# TRI_LED.net
KiCad netlist of a schematic drawn in EAGLE
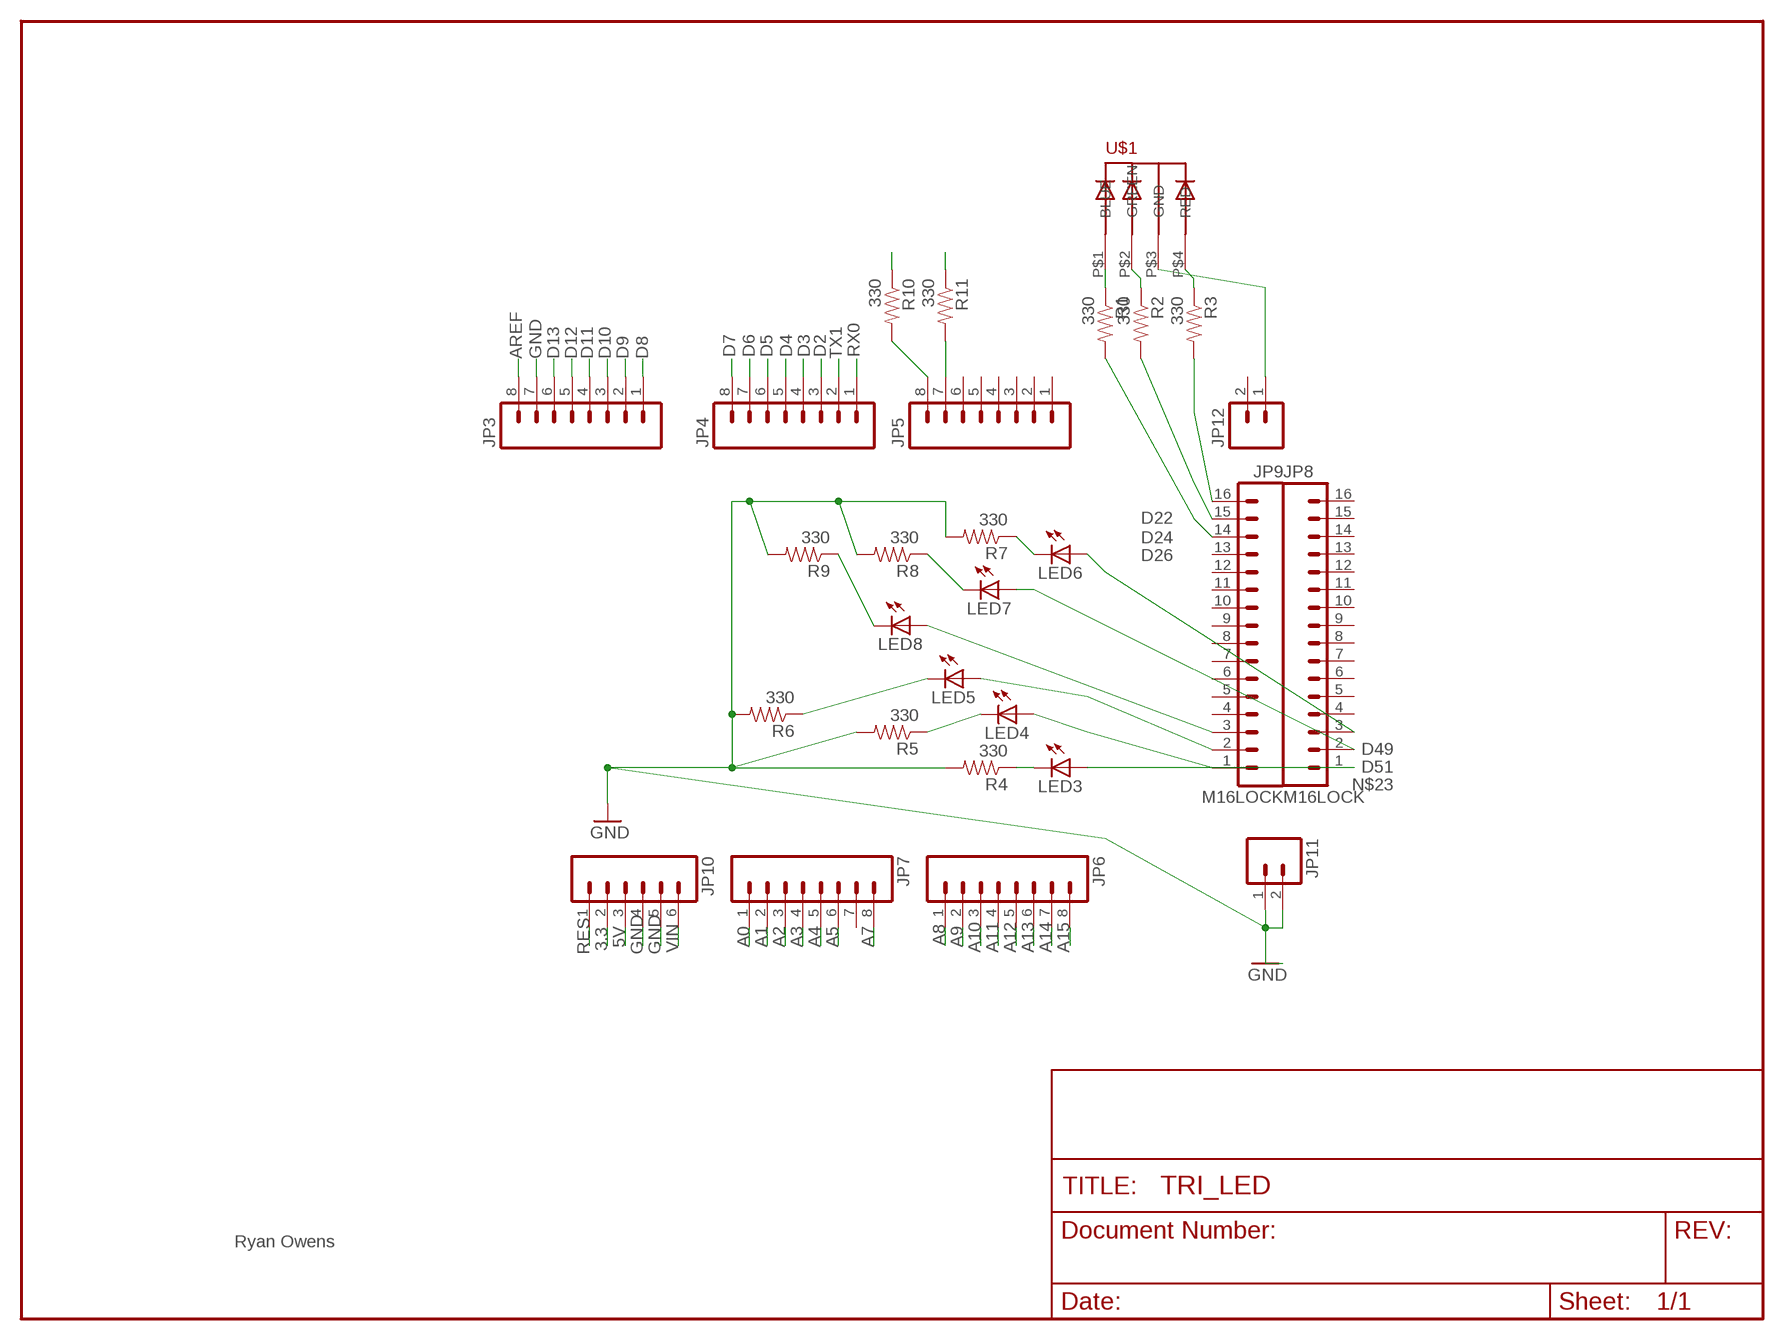
[diagram p0: schematic, sheet 1]

(export (version "E")
  (design (tool "Eeschema 10.0.6"))
  (components
    (comp (ref "JP3")
      (value "M08LOCK")
      (footprint "eagle-import:1X08_LOCK")
      (libsource (lib "eagle-import") (part "M08LOCK"))
    )
    (comp (ref "JP4")
      (value "M08LOCK")
      (footprint "eagle-import:1X08_LOCK")
      (libsource (lib "eagle-import") (part "M08LOCK"))
    )
    (comp (ref "JP5")
      (value "M08LOCK")
      (footprint "eagle-import:1X08_LOCK")
      (libsource (lib "eagle-import") (part "M08LOCK"))
    )
    (comp (ref "JP6")
      (value "M08LOCK")
      (footprint "eagle-import:1X08_LOCK")
      (libsource (lib "eagle-import") (part "M08LOCK"))
    )
    (comp (ref "JP7")
      (value "M08LOCK")
      (footprint "eagle-import:1X08_LOCK")
      (libsource (lib "eagle-import") (part "M08LOCK"))
    )
    (comp (ref "JP8")
      (value "M16LOCK")
      (footprint "eagle-import:1X16_LOCK")
      (libsource (lib "eagle-import") (part "M16LOCK"))
    )
    (comp (ref "JP9")
      (value "M16LOCK")
      (footprint "eagle-import:1X16_LOCK")
      (libsource (lib "eagle-import") (part "M16LOCK"))
    )
    (comp (ref "JP10")
      (value "M06LOCK")
      (footprint "eagle-import:1X06_LOCK")
      (libsource (lib "eagle-import") (part "M06LOCK"))
    )
    (comp (ref "JP11")
      (value "M02LOCK")
      (footprint "eagle-import:1X02_LOCK")
      (libsource (lib "eagle-import") (part "M02LOCK"))
    )
    (comp (ref "JP12")
      (value "M02LOCK")
      (footprint "eagle-import:1X02_LOCK")
      (libsource (lib "eagle-import") (part "M02LOCK"))
    )
    (comp (ref "LED3")
      (value "LED5MM")
      (footprint "eagle-import:LED5MM")
      (libsource (lib "eagle-import") (part "LED5MM"))
    )
    (comp (ref "LED4")
      (value "LED5MM")
      (footprint "eagle-import:LED5MM")
      (libsource (lib "eagle-import") (part "LED5MM"))
    )
    (comp (ref "LED5")
      (value "LED5MM")
      (footprint "eagle-import:LED5MM")
      (libsource (lib "eagle-import") (part "LED5MM"))
    )
    (comp (ref "LED6")
      (value "LED5MM")
      (footprint "eagle-import:LED5MM")
      (libsource (lib "eagle-import") (part "LED5MM"))
    )
    (comp (ref "LED7")
      (value "LED5MM")
      (footprint "eagle-import:LED5MM")
      (libsource (lib "eagle-import") (part "LED5MM"))
    )
    (comp (ref "LED8")
      (value "LED5MM")
      (footprint "eagle-import:LED5MM")
      (libsource (lib "eagle-import") (part "LED5MM"))
    )
    (comp (ref "R1")
      (value "330")
      (footprint "eagle-import:AXIAL-0.3")
      (libsource (lib "eagle-import") (part "RESISTORPTH1"))
    )
    (comp (ref "R2")
      (value "330")
      (footprint "eagle-import:AXIAL-0.3")
      (libsource (lib "eagle-import") (part "RESISTORPTH1"))
    )
    (comp (ref "R3")
      (value "330")
      (footprint "eagle-import:AXIAL-0.3")
      (libsource (lib "eagle-import") (part "RESISTORPTH1"))
    )
    (comp (ref "R4")
      (value "330")
      (footprint "eagle-import:AXIAL-0.3")
      (libsource (lib "eagle-import") (part "RESISTORPTH1"))
    )
    (comp (ref "R5")
      (value "330")
      (footprint "eagle-import:AXIAL-0.3")
      (libsource (lib "eagle-import") (part "RESISTORPTH1"))
    )
    (comp (ref "R6")
      (value "330")
      (footprint "eagle-import:AXIAL-0.3")
      (libsource (lib "eagle-import") (part "RESISTORPTH1"))
    )
    (comp (ref "R7")
      (value "330")
      (footprint "eagle-import:AXIAL-0.3")
      (libsource (lib "eagle-import") (part "RESISTORPTH1"))
    )
    (comp (ref "R8")
      (value "330")
      (footprint "eagle-import:AXIAL-0.3")
      (libsource (lib "eagle-import") (part "RESISTORPTH1"))
    )
    (comp (ref "R9")
      (value "330")
      (footprint "eagle-import:AXIAL-0.3")
      (libsource (lib "eagle-import") (part "RESISTORPTH1"))
    )
    (comp (ref "R10")
      (value "330")
      (footprint "eagle-import:AXIAL-0.3")
      (libsource (lib "eagle-import") (part "RESISTORPTH1"))
    )
    (comp (ref "R11")
      (value "330")
      (footprint "eagle-import:AXIAL-0.3")
      (libsource (lib "eagle-import") (part "RESISTORPTH1"))
    )
    (comp (ref "U$1")
      (value "5MMRGBLED")
      (footprint "eagle-import:LED5MMRGB")
      (libsource (lib "eagle-import") (part "5MMRGBLED"))
    )
  )
  (nets
    (net (code "1") (name "/3.3") (class "Default")
      (node (ref "JP10") (pin "2") (pinfunction "2_2") (pintype "passive"))
    )
    (net (code "2") (name "/5V") (class "Default")
      (node (ref "JP10") (pin "3") (pinfunction "3_3") (pintype "passive"))
    )
    (net (code "3") (name "/A0") (class "Default")
      (node (ref "JP7") (pin "1") (pinfunction "1_1") (pintype "passive"))
    )
    (net (code "4") (name "/A1") (class "Default")
      (node (ref "JP7") (pin "2") (pinfunction "2_2") (pintype "passive"))
    )
    (net (code "5") (name "/A2") (class "Default")
      (node (ref "JP7") (pin "3") (pinfunction "3_3") (pintype "passive"))
    )
    (net (code "6") (name "/A3") (class "Default")
      (node (ref "JP7") (pin "4") (pinfunction "4_4") (pintype "passive"))
    )
    (net (code "7") (name "/A4") (class "Default")
      (node (ref "JP7") (pin "5") (pinfunction "5_5") (pintype "passive"))
    )
    (net (code "8") (name "/A5") (class "Default")
      (node (ref "JP7") (pin "6") (pinfunction "6_6") (pintype "passive"))
    )
    (net (code "9") (name "/A7") (class "Default")
      (node (ref "JP7") (pin "8") (pinfunction "8_8") (pintype "passive"))
    )
    (net (code "10") (name "/A8") (class "Default")
      (node (ref "JP6") (pin "1") (pinfunction "1_1") (pintype "passive"))
    )
    (net (code "11") (name "/A9") (class "Default")
      (node (ref "JP6") (pin "2") (pinfunction "2_2") (pintype "passive"))
    )
    (net (code "12") (name "/A10") (class "Default")
      (node (ref "JP6") (pin "3") (pinfunction "3_3") (pintype "passive"))
    )
    (net (code "13") (name "/A11") (class "Default")
      (node (ref "JP6") (pin "4") (pinfunction "4_4") (pintype "passive"))
    )
    (net (code "14") (name "/A12") (class "Default")
      (node (ref "JP6") (pin "5") (pinfunction "5_5") (pintype "passive"))
    )
    (net (code "15") (name "/A13") (class "Default")
      (node (ref "JP6") (pin "6") (pinfunction "6_6") (pintype "passive"))
    )
    (net (code "16") (name "/A14") (class "Default")
      (node (ref "JP6") (pin "7") (pinfunction "7_7") (pintype "passive"))
    )
    (net (code "17") (name "/A15") (class "Default")
      (node (ref "JP6") (pin "8") (pinfunction "8_8") (pintype "passive"))
    )
    (net (code "18") (name "/AREF") (class "Default")
      (node (ref "JP3") (pin "8") (pinfunction "8_8") (pintype "passive"))
    )
    (net (code "19") (name "/D2") (class "Default")
      (node (ref "JP4") (pin "3") (pinfunction "3_3") (pintype "passive"))
    )
    (net (code "20") (name "/D3") (class "Default")
      (node (ref "JP4") (pin "4") (pinfunction "4_4") (pintype "passive"))
    )
    (net (code "21") (name "/D4") (class "Default")
      (node (ref "JP4") (pin "5") (pinfunction "5_5") (pintype "passive"))
    )
    (net (code "22") (name "/D5") (class "Default")
      (node (ref "JP4") (pin "6") (pinfunction "6_6") (pintype "passive"))
    )
    (net (code "23") (name "/D6") (class "Default")
      (node (ref "JP4") (pin "7") (pinfunction "7_7") (pintype "passive"))
    )
    (net (code "24") (name "/D7") (class "Default")
      (node (ref "JP4") (pin "8") (pinfunction "8_8") (pintype "passive"))
    )
    (net (code "25") (name "/D8") (class "Default")
      (node (ref "JP3") (pin "1") (pinfunction "1_1") (pintype "passive"))
    )
    (net (code "26") (name "/D9") (class "Default")
      (node (ref "JP3") (pin "2") (pinfunction "2_2") (pintype "passive"))
    )
    (net (code "27") (name "/D10") (class "Default")
      (node (ref "JP3") (pin "3") (pinfunction "3_3") (pintype "passive"))
    )
    (net (code "28") (name "/D11") (class "Default")
      (node (ref "JP3") (pin "4") (pinfunction "4_4") (pintype "passive"))
    )
    (net (code "29") (name "/D12") (class "Default")
      (node (ref "JP3") (pin "5") (pinfunction "5_5") (pintype "passive"))
    )
    (net (code "30") (name "/D13") (class "Default")
      (node (ref "JP3") (pin "6") (pinfunction "6_6") (pintype "passive"))
    )
    (net (code "31") (name "/D22") (class "Default")
      (node (ref "JP9") (pin "1") (pinfunction "1_1") (pintype "passive"))
      (node (ref "LED4") (pin "A") (pinfunction "A_A") (pintype "passive"))
    )
    (net (code "32") (name "/D24") (class "Default")
      (node (ref "JP9") (pin "2") (pinfunction "2_2") (pintype "passive"))
      (node (ref "LED5") (pin "A") (pinfunction "A_A") (pintype "passive"))
    )
    (net (code "33") (name "/D26") (class "Default")
      (node (ref "JP9") (pin "3") (pinfunction "3_3") (pintype "passive"))
      (node (ref "LED8") (pin "A") (pinfunction "A_A") (pintype "passive"))
    )
    (net (code "34") (name "/D49") (class "Default")
      (node (ref "JP8") (pin "3") (pinfunction "3_3") (pintype "passive"))
      (node (ref "LED6") (pin "A") (pinfunction "A_A") (pintype "passive"))
    )
    (net (code "35") (name "/D51") (class "Default")
      (node (ref "JP8") (pin "2") (pinfunction "2_2") (pintype "passive"))
      (node (ref "LED7") (pin "A") (pinfunction "A_A") (pintype "passive"))
    )
    (net (code "36") (name "/N$23") (class "Default")
      (node (ref "JP8") (pin "1") (pinfunction "1_1") (pintype "passive"))
      (node (ref "LED3") (pin "A") (pinfunction "A_A") (pintype "passive"))
    )
    (net (code "37") (name "/RES") (class "Default")
      (node (ref "JP10") (pin "1") (pinfunction "1_1") (pintype "passive"))
    )
    (net (code "38") (name "/RX0") (class "Default")
      (node (ref "JP4") (pin "1") (pinfunction "1_1") (pintype "passive"))
    )
    (net (code "39") (name "/TX1") (class "Default")
      (node (ref "JP4") (pin "2") (pinfunction "2_2") (pintype "passive"))
    )
    (net (code "40") (name "/VIN") (class "Default")
      (node (ref "JP10") (pin "6") (pinfunction "6_6") (pintype "passive"))
    )
    (net (code "41") (name "GND") (class "Default")
      (node (ref "JP10") (pin "4") (pinfunction "4_4") (pintype "passive"))
      (node (ref "JP10") (pin "5") (pinfunction "5_5") (pintype "passive"))
      (node (ref "JP11") (pin "1") (pinfunction "1_1") (pintype "passive"))
      (node (ref "JP11") (pin "2") (pinfunction "2_2") (pintype "passive"))
      (node (ref "JP3") (pin "7") (pinfunction "7_7") (pintype "passive"))
      (node (ref "R4") (pin "P$2") (pinfunction "2_P$2") (pintype "passive"))
      (node (ref "R5") (pin "P$2") (pinfunction "2_P$2") (pintype "passive"))
      (node (ref "R6") (pin "P$2") (pinfunction "2_P$2") (pintype "passive"))
      (node (ref "R7") (pin "P$2") (pinfunction "2_P$2") (pintype "passive"))
      (node (ref "R8") (pin "P$2") (pinfunction "2_P$2") (pintype "passive"))
      (node (ref "R9") (pin "P$2") (pinfunction "2_P$2") (pintype "passive"))
    )
    (net (code "42") (name "Net-(LED3-C)") (class "Default")
      (node (ref "LED3") (pin "K") (pinfunction "C_K") (pintype "passive"))
      (node (ref "R4") (pin "P$1") (pinfunction "1_P$1") (pintype "passive"))
    )
    (net (code "43") (name "Net-(LED4-C)") (class "Default")
      (node (ref "LED4") (pin "K") (pinfunction "C_K") (pintype "passive"))
      (node (ref "R5") (pin "P$1") (pinfunction "1_P$1") (pintype "passive"))
    )
    (net (code "44") (name "Net-(LED5-C)") (class "Default")
      (node (ref "LED5") (pin "K") (pinfunction "C_K") (pintype "passive"))
      (node (ref "R6") (pin "P$1") (pinfunction "1_P$1") (pintype "passive"))
    )
    (net (code "45") (name "Net-(LED6-C)") (class "Default")
      (node (ref "LED6") (pin "K") (pinfunction "C_K") (pintype "passive"))
      (node (ref "R7") (pin "P$1") (pinfunction "1_P$1") (pintype "passive"))
    )
    (net (code "46") (name "Net-(LED7-C)") (class "Default")
      (node (ref "LED7") (pin "K") (pinfunction "C_K") (pintype "passive"))
      (node (ref "R8") (pin "P$1") (pinfunction "1_P$1") (pintype "passive"))
    )
    (net (code "47") (name "Net-(LED8-C)") (class "Default")
      (node (ref "LED8") (pin "K") (pinfunction "C_K") (pintype "passive"))
      (node (ref "R9") (pin "P$1") (pinfunction "1_P$1") (pintype "passive"))
    )
    (net (code "48") (name "Net-(R1-1)") (class "Default")
      (node (ref "R1") (pin "P$1") (pinfunction "1_P$1") (pintype "passive"))
      (node (ref "U$1") (pin "P$1") (pinfunction "BLUE_P$1") (pintype "bidirectional"))
    )
    (net (code "49") (name "Net-(R1-2)") (class "Default")
      (node (ref "JP9") (pin "14") (pinfunction "14_14") (pintype "passive"))
      (node (ref "R1") (pin "P$2") (pinfunction "2_P$2") (pintype "passive"))
    )
    (net (code "50") (name "Net-(R2-1)") (class "Default")
      (node (ref "R2") (pin "P$1") (pinfunction "1_P$1") (pintype "passive"))
      (node (ref "U$1") (pin "P$2") (pinfunction "GREEN_P$2") (pintype "bidirectional"))
    )
    (net (code "51") (name "Net-(R2-2)") (class "Default")
      (node (ref "JP9") (pin "15") (pinfunction "15_15") (pintype "passive"))
      (node (ref "R2") (pin "P$2") (pinfunction "2_P$2") (pintype "passive"))
    )
    (net (code "52") (name "Net-(R3-1)") (class "Default")
      (node (ref "R3") (pin "P$1") (pinfunction "1_P$1") (pintype "passive"))
      (node (ref "U$1") (pin "P$4") (pinfunction "RED_P$4") (pintype "bidirectional"))
    )
    (net (code "53") (name "Net-(R3-2)") (class "Default")
      (node (ref "JP9") (pin "16") (pinfunction "16_16") (pintype "passive"))
      (node (ref "R3") (pin "P$2") (pinfunction "2_P$2") (pintype "passive"))
    )
    (net (code "54") (name "Net-(R10-2)") (class "Default")
      (node (ref "JP5") (pin "8") (pinfunction "8_8") (pintype "passive"))
      (node (ref "R10") (pin "P$2") (pinfunction "2_P$2") (pintype "passive"))
    )
    (net (code "55") (name "Net-(R11-2)") (class "Default")
      (node (ref "JP5") (pin "7") (pinfunction "7_7") (pintype "passive"))
      (node (ref "R11") (pin "P$2") (pinfunction "2_P$2") (pintype "passive"))
    )
    (net (code "56") (name "Net-(U$1-GND)") (class "Default")
      (node (ref "JP12") (pin "1") (pinfunction "1_1") (pintype "passive"))
      (node (ref "U$1") (pin "P$3") (pinfunction "GND_P$3") (pintype "bidirectional"))
    )
    (net (code "57") (name "unconnected-(JP5-Pad1)") (class "Default")
      (node (ref "JP5") (pin "1") (pinfunction "1_1") (pintype "passive"))
    )
    (net (code "58") (name "unconnected-(JP5-Pad2)") (class "Default")
      (node (ref "JP5") (pin "2") (pinfunction "2_2") (pintype "passive"))
    )
    (net (code "59") (name "unconnected-(JP5-Pad3)") (class "Default")
      (node (ref "JP5") (pin "3") (pinfunction "3_3") (pintype "passive"))
    )
    (net (code "60") (name "unconnected-(JP5-Pad4)") (class "Default")
      (node (ref "JP5") (pin "4") (pinfunction "4_4") (pintype "passive"))
    )
    (net (code "61") (name "unconnected-(JP5-Pad5)") (class "Default")
      (node (ref "JP5") (pin "5") (pinfunction "5_5") (pintype "passive"))
    )
    (net (code "62") (name "unconnected-(JP5-Pad6)") (class "Default")
      (node (ref "JP5") (pin "6") (pinfunction "6_6") (pintype "passive"))
    )
    (net (code "63") (name "unconnected-(JP7-Pad7)") (class "Default")
      (node (ref "JP7") (pin "7") (pinfunction "7_7") (pintype "passive"))
    )
    (net (code "64") (name "unconnected-(JP8-Pad4)") (class "Default")
      (node (ref "JP8") (pin "4") (pinfunction "4_4") (pintype "passive"))
    )
    (net (code "65") (name "unconnected-(JP8-Pad5)") (class "Default")
      (node (ref "JP8") (pin "5") (pinfunction "5_5") (pintype "passive"))
    )
    (net (code "66") (name "unconnected-(JP8-Pad6)") (class "Default")
      (node (ref "JP8") (pin "6") (pinfunction "6_6") (pintype "passive"))
    )
    (net (code "67") (name "unconnected-(JP8-Pad7)") (class "Default")
      (node (ref "JP8") (pin "7") (pinfunction "7_7") (pintype "passive"))
    )
    (net (code "68") (name "unconnected-(JP8-Pad8)") (class "Default")
      (node (ref "JP8") (pin "8") (pinfunction "8_8") (pintype "passive"))
    )
    (net (code "69") (name "unconnected-(JP8-Pad9)") (class "Default")
      (node (ref "JP8") (pin "9") (pinfunction "9_9") (pintype "passive"))
    )
    (net (code "70") (name "unconnected-(JP8-Pad10)") (class "Default")
      (node (ref "JP8") (pin "10") (pinfunction "10_10") (pintype "passive"))
    )
    (net (code "71") (name "unconnected-(JP8-Pad11)") (class "Default")
      (node (ref "JP8") (pin "11") (pinfunction "11_11") (pintype "passive"))
    )
    (net (code "72") (name "unconnected-(JP8-Pad12)") (class "Default")
      (node (ref "JP8") (pin "12") (pinfunction "12_12") (pintype "passive"))
    )
    (net (code "73") (name "unconnected-(JP8-Pad13)") (class "Default")
      (node (ref "JP8") (pin "13") (pinfunction "13_13") (pintype "passive"))
    )
    (net (code "74") (name "unconnected-(JP8-Pad14)") (class "Default")
      (node (ref "JP8") (pin "14") (pinfunction "14_14") (pintype "passive"))
    )
    (net (code "75") (name "unconnected-(JP8-Pad15)") (class "Default")
      (node (ref "JP8") (pin "15") (pinfunction "15_15") (pintype "passive"))
    )
    (net (code "76") (name "unconnected-(JP8-Pad16)") (class "Default")
      (node (ref "JP8") (pin "16") (pinfunction "16_16") (pintype "passive"))
    )
    (net (code "77") (name "unconnected-(JP9-Pad4)") (class "Default")
      (node (ref "JP9") (pin "4") (pinfunction "4_4") (pintype "passive"))
    )
    (net (code "78") (name "unconnected-(JP9-Pad5)") (class "Default")
      (node (ref "JP9") (pin "5") (pinfunction "5_5") (pintype "passive"))
    )
    (net (code "79") (name "unconnected-(JP9-Pad6)") (class "Default")
      (node (ref "JP9") (pin "6") (pinfunction "6_6") (pintype "passive"))
    )
    (net (code "80") (name "unconnected-(JP9-Pad7)") (class "Default")
      (node (ref "JP9") (pin "7") (pinfunction "7_7") (pintype "passive"))
    )
    (net (code "81") (name "unconnected-(JP9-Pad8)") (class "Default")
      (node (ref "JP9") (pin "8") (pinfunction "8_8") (pintype "passive"))
    )
    (net (code "82") (name "unconnected-(JP9-Pad9)") (class "Default")
      (node (ref "JP9") (pin "9") (pinfunction "9_9") (pintype "passive"))
    )
    (net (code "83") (name "unconnected-(JP9-Pad10)") (class "Default")
      (node (ref "JP9") (pin "10") (pinfunction "10_10") (pintype "passive"))
    )
    (net (code "84") (name "unconnected-(JP9-Pad11)") (class "Default")
      (node (ref "JP9") (pin "11") (pinfunction "11_11") (pintype "passive"))
    )
    (net (code "85") (name "unconnected-(JP9-Pad12)") (class "Default")
      (node (ref "JP9") (pin "12") (pinfunction "12_12") (pintype "passive"))
    )
    (net (code "86") (name "unconnected-(JP9-Pad13)") (class "Default")
      (node (ref "JP9") (pin "13") (pinfunction "13_13") (pintype "passive"))
    )
    (net (code "87") (name "unconnected-(JP12-Pad2)") (class "Default")
      (node (ref "JP12") (pin "2") (pinfunction "2_2") (pintype "passive"))
    )
    (net (code "88") (name "unconnected-(R10-1-PadP$1)") (class "Default")
      (node (ref "R10") (pin "P$1") (pinfunction "1_P$1") (pintype "passive"))
    )
    (net (code "89") (name "unconnected-(R11-1-PadP$1)") (class "Default")
      (node (ref "R11") (pin "P$1") (pinfunction "1_P$1") (pintype "passive"))
    )
  )
)
